# CPU-POWER.net
KiCad netlist of a schematic drawn in Altium Designer
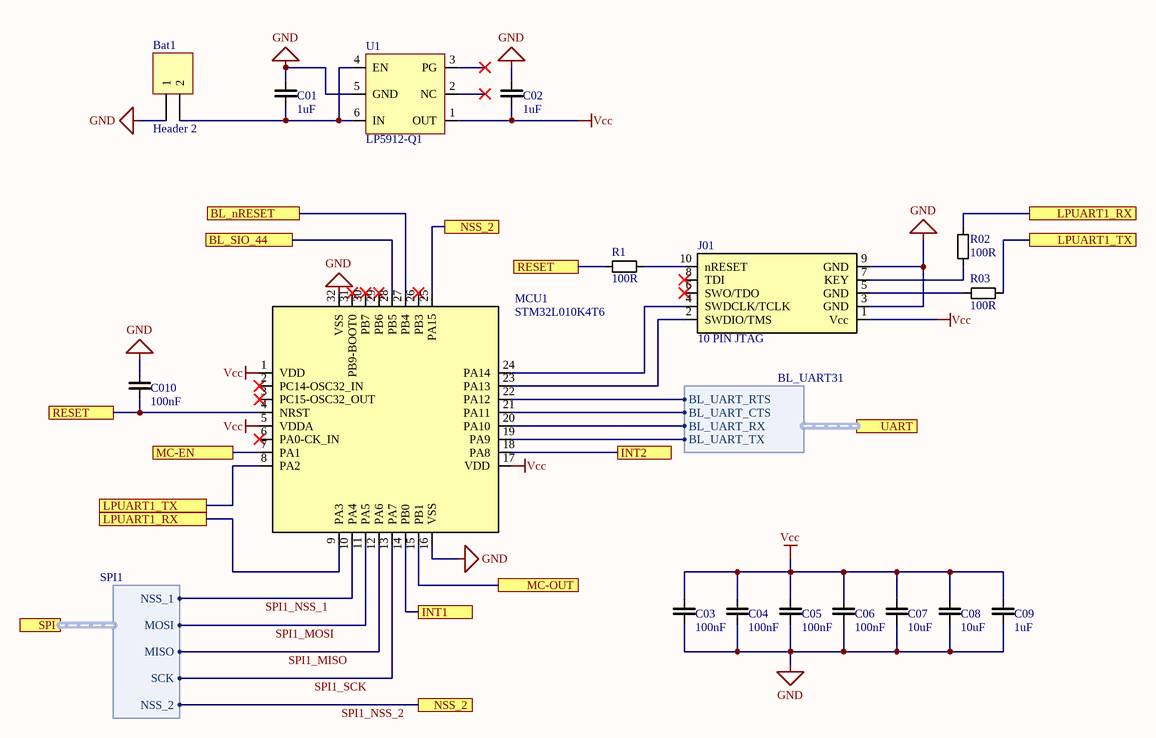
[diagram p0: CPU-POWER.SchDoc]

(export (version "E")
  (design (tool "Eeschema 10.0.6"))
  (components
    (comp (ref "Bat1")
      (value "Header 2")
      (footprint "HDR1X2")
      (description "Header, 2-Pin")
      (fields (field (name "PUBLISHER") "Altium Limited"))
      (libsource (lib "Miscellaneous Connectors") (part "Header 2"))
    )
    (comp (ref "C01") (value "1uF") (description "Ceramic capacitor") (libsource (lib "Cap") (part "Cap")))
    (comp (ref "C02") (value "1uF") (description "Ceramic capacitor") (libsource (lib "Cap") (part "Cap")))
    (comp (ref "C03") (value "100nF") (description "Ceramic capacitor") (libsource (lib "Cap") (part "Cap")))
    (comp (ref "C04") (value "100nF") (description "Ceramic capacitor") (libsource (lib "Cap") (part "Cap")))
    (comp (ref "C05") (value "100nF") (description "Ceramic capacitor") (libsource (lib "Cap") (part "Cap")))
    (comp (ref "C06") (value "100nF") (description "Ceramic capacitor") (libsource (lib "Cap") (part "Cap")))
    (comp (ref "C07") (value "10uF") (description "Ceramic capacitor") (libsource (lib "Cap") (part "Cap")))
    (comp (ref "C08") (value "10uF") (description "Ceramic capacitor") (libsource (lib "Cap") (part "Cap")))
    (comp (ref "C09") (value "1uF") (description "Ceramic capacitor") (libsource (lib "Cap") (part "Cap")))
    (comp (ref "C010") (value "100nF") (description "Ceramic capacitor") (libsource (lib "Cap") (part "Cap")))
    (comp (ref "J01") (value "10 PIN JTAG") (libsource (lib "parts1") (part "JTAG")))
    (comp (ref "MCU1") (value "STM32L010K4T6") (libsource (lib "parts1") (part "CPU32p")))
    (comp (ref "R1") (value "100R") (description "Resistor") (libsource (lib "RES") (part "RES")))
    (comp (ref "R02") (value "100R") (description "Resistor") (libsource (lib "RES") (part "RES")))
    (comp (ref "R03") (value "100R") (description "Resistor") (libsource (lib "RES") (part "RES")))
    (comp (ref "U1") (value "LP5912-Q1") (libsource (lib "parts1") (part "STAB")))
  )
  (nets
    (net (code "3") (name "/BL_SIO_44") (class "Default")
      (node (ref "MCU1") (pin "28") (pinfunction "PB5_28") (pintype "passive"))
    )
    (net (code "4") (name "/BL_UART_CTS") (class "Default")
      (node (ref "MCU1") (pin "21") (pinfunction "PA11_21") (pintype "passive"))
    )
    (net (code "5") (name "/BL_UART_RTS") (class "Default")
      (node (ref "MCU1") (pin "22") (pinfunction "PA12_22") (pintype "passive"))
    )
    (net (code "6") (name "/BL_UART_RX") (class "Default")
      (node (ref "MCU1") (pin "20") (pinfunction "PA10_20") (pintype "passive"))
    )
    (net (code "7") (name "/BL_UART_TX") (class "Default")
      (node (ref "MCU1") (pin "19") (pinfunction "PA9_19") (pintype "passive"))
    )
    (net (code "8") (name "/BL_nRESET") (class "Default")
      (node (ref "MCU1") (pin "27") (pinfunction "PB4_27") (pintype "passive"))
    )
    (net (code "9") (name "/INT1") (class "Default")
      (node (ref "MCU1") (pin "14") (pinfunction "PB0_14") (pintype "passive"))
    )
    (net (code "10") (name "/INT2") (class "Default")
      (node (ref "MCU1") (pin "18") (pinfunction "PA8_18") (pintype "passive"))
    )
    (net (code "11") (name "/LPUART1_RX") (class "Default")
      (node (ref "MCU1") (pin "9") (pinfunction "PA3_9") (pintype "passive"))
      (node (ref "R02") (pin "2") (pinfunction "2_2") (pintype "passive"))
    )
    (net (code "12") (name "/LPUART1_TX") (class "Default")
      (node (ref "MCU1") (pin "8") (pinfunction "PA2_8") (pintype "passive"))
      (node (ref "R03") (pin "1") (pinfunction "1_1") (pintype "passive"))
    )
    (net (code "13") (name "/MC-EN") (class "Default")
      (node (ref "MCU1") (pin "7") (pinfunction "PA1_7") (pintype "passive"))
    )
    (net (code "14") (name "/MC-OUT") (class "Default")
      (node (ref "MCU1") (pin "15") (pinfunction "PB1_15") (pintype "passive"))
    )
    (net (code "15") (name "/RESET") (class "Default")
      (node (ref "C010") (pin "1") (pinfunction "1_1") (pintype "passive"))
      (node (ref "MCU1") (pin "4") (pinfunction "NRST_4") (pintype "passive"))
      (node (ref "R1") (pin "1") (pinfunction "1_1") (pintype "passive"))
    )
    (net (code "16") (name "/SPI1_MISO") (class "Default")
      (node (ref "MCU1") (pin "12") (pinfunction "PA6_12") (pintype "passive"))
    )
    (net (code "17") (name "/SPI1_MOSI") (class "Default")
      (node (ref "MCU1") (pin "11") (pinfunction "PA5_11") (pintype "passive"))
    )
    (net (code "18") (name "/SPI1_NSS_1") (class "Default")
      (node (ref "MCU1") (pin "10") (pinfunction "PA4_10") (pintype "passive"))
    )
    (net (code "19") (name "/SPI1_NSS_2") (class "Default")
      (node (ref "MCU1") (pin "25") (pinfunction "PA15_25") (pintype "passive"))
    )
    (net (code "20") (name "/SPI1_SCK") (class "Default")
      (node (ref "MCU1") (pin "13") (pinfunction "PA7_13") (pintype "passive"))
    )
    (net (code "23") (name "GND") (class "Default")
      (node (ref "Bat1") (pin "1") (pinfunction "1_1") (pintype "passive"))
      (node (ref "C01") (pin "2") (pinfunction "2_2") (pintype "passive"))
      (node (ref "C010") (pin "2") (pinfunction "2_2") (pintype "passive"))
      (node (ref "C02") (pin "2") (pinfunction "2_2") (pintype "passive"))
      (node (ref "C03") (pin "1") (pinfunction "1_1") (pintype "passive"))
      (node (ref "C04") (pin "1") (pinfunction "1_1") (pintype "passive"))
      (node (ref "C05") (pin "1") (pinfunction "1_1") (pintype "passive"))
      (node (ref "C06") (pin "1") (pinfunction "1_1") (pintype "passive"))
      (node (ref "C07") (pin "1") (pinfunction "1_1") (pintype "passive"))
      (node (ref "C08") (pin "1") (pinfunction "1_1") (pintype "passive"))
      (node (ref "C09") (pin "1") (pinfunction "1_1") (pintype "passive"))
      (node (ref "J01") (pin "3") (pinfunction "GND_3") (pintype "passive"))
      (node (ref "J01") (pin "9") (pinfunction "GND_9") (pintype "passive"))
      (node (ref "MCU1") (pin "16") (pinfunction "VSS_16") (pintype "passive"))
      (node (ref "MCU1") (pin "32") (pinfunction "VSS_32") (pintype "passive"))
      (node (ref "U1") (pin "5") (pinfunction "GND_5") (pintype "passive"))
    )
    (net (code "24") (name "Net-(J01-GND-Pad5)") (class "Default")
      (node (ref "J01") (pin "5") (pinfunction "GND_5") (pintype "passive"))
      (node (ref "R03") (pin "2") (pinfunction "2_2") (pintype "passive"))
    )
    (net (code "25") (name "Net-(J01-KEY)") (class "Default")
      (node (ref "J01") (pin "7") (pinfunction "KEY_7") (pintype "passive"))
      (node (ref "R02") (pin "1") (pinfunction "1_1") (pintype "passive"))
    )
    (net (code "26") (name "Net-(J01-SWDCLK{slash}TCLK)") (class "Default")
      (node (ref "J01") (pin "4") (pinfunction "SWDCLK/TCLK_4") (pintype "passive"))
      (node (ref "MCU1") (pin "24") (pinfunction "PA14_24") (pintype "passive"))
    )
    (net (code "27") (name "Net-(J01-SWDIO{slash}TMS)") (class "Default")
      (node (ref "J01") (pin "2") (pinfunction "SWDIO/TMS_2") (pintype "passive"))
      (node (ref "MCU1") (pin "23") (pinfunction "PA13_23") (pintype "passive"))
    )
    (net (code "28") (name "Net-(J01-nRESET)") (class "Default")
      (node (ref "J01") (pin "10") (pinfunction "nRESET_10") (pintype "passive"))
      (node (ref "R1") (pin "2") (pinfunction "2_2") (pintype "passive"))
    )
    (net (code "29") (name "Net-(U1-EN)") (class "Default")
      (node (ref "Bat1") (pin "2") (pinfunction "2_2") (pintype "passive"))
      (node (ref "C01") (pin "1") (pinfunction "1_1") (pintype "passive"))
      (node (ref "U1") (pin "4") (pinfunction "EN_4") (pintype "passive"))
      (node (ref "U1") (pin "6") (pinfunction "IN_6") (pintype "passive"))
    )
    (net (code "30") (name "Vcc") (class "Default")
      (node (ref "C02") (pin "1") (pinfunction "1_1") (pintype "passive"))
      (node (ref "C03") (pin "2") (pinfunction "2_2") (pintype "passive"))
      (node (ref "C04") (pin "2") (pinfunction "2_2") (pintype "passive"))
      (node (ref "C05") (pin "2") (pinfunction "2_2") (pintype "passive"))
      (node (ref "C06") (pin "2") (pinfunction "2_2") (pintype "passive"))
      (node (ref "C07") (pin "2") (pinfunction "2_2") (pintype "passive"))
      (node (ref "C08") (pin "2") (pinfunction "2_2") (pintype "passive"))
      (node (ref "C09") (pin "2") (pinfunction "2_2") (pintype "passive"))
      (node (ref "J01") (pin "1") (pinfunction "Vcc_1") (pintype "passive"))
      (node (ref "MCU1") (pin "1") (pinfunction "VDD_1") (pintype "passive"))
      (node (ref "MCU1") (pin "17") (pinfunction "VDD_17") (pintype "passive"))
      (node (ref "MCU1") (pin "5") (pinfunction "VDDA_5") (pintype "passive"))
      (node (ref "U1") (pin "1") (pinfunction "OUT_1") (pintype "passive"))
    )
    (net (code "31") (name "unconnected-(J01-SWO{slash}TDO-Pad6)") (class "Default")
      (node (ref "J01") (pin "6") (pinfunction "SWO/TDO_6") (pintype "passive+no_connect"))
    )
    (net (code "32") (name "unconnected-(J01-TDI-Pad8)") (class "Default")
      (node (ref "J01") (pin "8") (pinfunction "TDI_8") (pintype "passive+no_connect"))
    )
    (net (code "33") (name "unconnected-(MCU1-PA0-CK_IN-Pad6)") (class "Default")
      (node (ref "MCU1") (pin "6") (pinfunction "PA0-CK_IN_6") (pintype "passive+no_connect"))
    )
    (net (code "34") (name "unconnected-(MCU1-PB3-Pad26)") (class "Default")
      (node (ref "MCU1") (pin "26") (pinfunction "PB3_26") (pintype "passive+no_connect"))
    )
    (net (code "35") (name "unconnected-(MCU1-PB6-Pad29)") (class "Default")
      (node (ref "MCU1") (pin "29") (pinfunction "PB6_29") (pintype "passive+no_connect"))
    )
    (net (code "36") (name "unconnected-(MCU1-PB7-Pad30)") (class "Default")
      (node (ref "MCU1") (pin "30") (pinfunction "PB7_30") (pintype "passive+no_connect"))
    )
    (net (code "37") (name "unconnected-(MCU1-PB9-BOOT0-Pad31)") (class "Default")
      (node (ref "MCU1") (pin "31") (pinfunction "PB9-BOOT0_31") (pintype "passive+no_connect"))
    )
    (net (code "38") (name "unconnected-(MCU1-PC14-OSC32_IN-Pad2)") (class "Default")
      (node (ref "MCU1") (pin "2") (pinfunction "PC14-OSC32_IN_2") (pintype "passive+no_connect"))
    )
    (net (code "39") (name "unconnected-(MCU1-PC15-OSC32_OUT-Pad3)") (class "Default")
      (node (ref "MCU1") (pin "3") (pinfunction "PC15-OSC32_OUT_3") (pintype "passive+no_connect"))
    )
    (net (code "40") (name "unconnected-(U1-NC-Pad2)") (class "Default")
      (node (ref "U1") (pin "2") (pinfunction "NC_2") (pintype "passive+no_connect"))
    )
    (net (code "41") (name "unconnected-(U1-PG-Pad3)") (class "Default")
      (node (ref "U1") (pin "3") (pinfunction "PG_3") (pintype "passive+no_connect"))
    )
  )
)
